# 03_RK808.net
KiCad netlist of a schematic drawn in Altium Designer
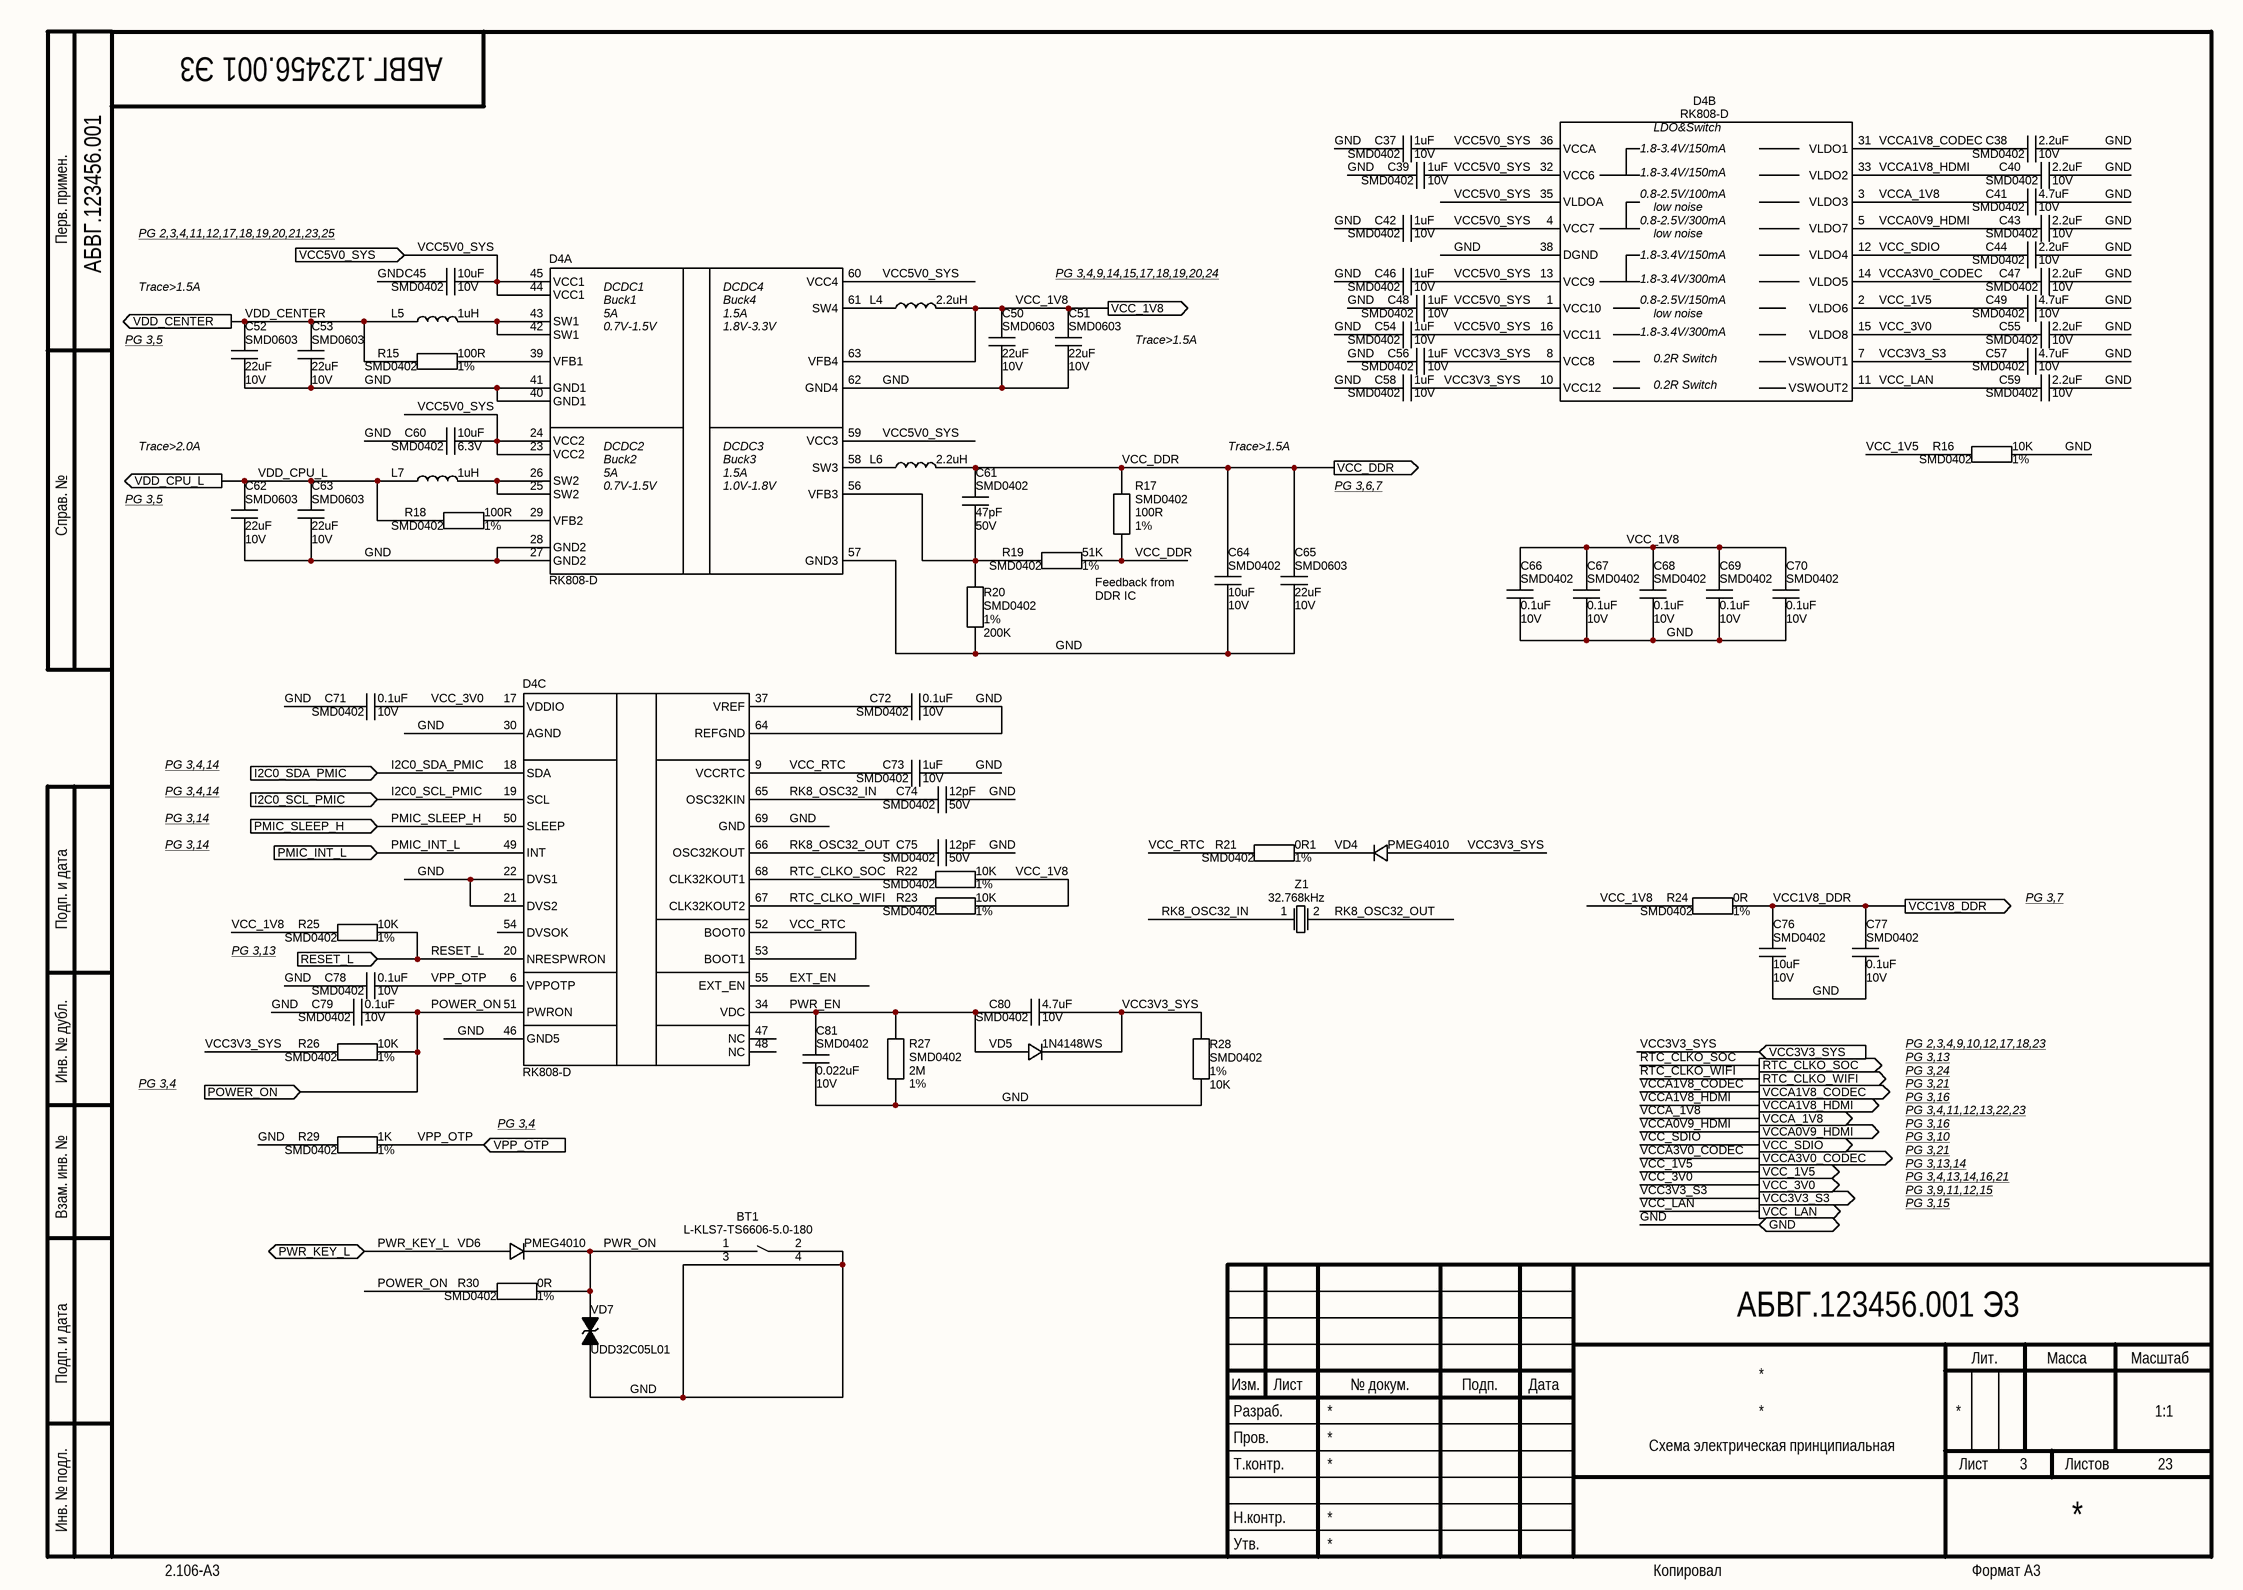
[diagram p0: 03 RK808.SchDoc]

(export (version "E")
  (design (tool "Eeschema 10.0.6"))
  (components
    (comp (ref "BT1")
      (value "L-KLS7-TS6606-5.0-180")
      (footprint "Didur_PcbLib_1:L-KLS7-TS6606-5.0-180")
      (libsource (lib "Didur_SchLib_1") (part "Button_Corner_4pin"))
    )
    (comp (ref "C37")
      (value "1uF")
      (footprint "Didur_PcbLib_1:CAP_SMD_0402")
      (fields
        (field (name "PACKAGE") "SMD0402")
        (field (name "PARTNUMBER") "CC0402KRX5R6BB105")
        (field (name "VOLTAGE") "10V")
      )
      (libsource (lib "Didur_SchLib_1") (part "Ceramic_Cap"))
    )
    (comp (ref "C38")
      (value "2.2uF")
      (footprint "Didur_PcbLib_1:CAP_SMD_0402")
      (fields
        (field (name "PACKAGE") "SMD0402")
        (field (name "PARTNUMBER") "CC0402KRX5R6BB225")
        (field (name "VOLTAGE") "10V")
      )
      (libsource (lib "Didur_SchLib_1") (part "Ceramic_Cap"))
    )
    (comp (ref "C39")
      (value "1uF")
      (footprint "Didur_PcbLib_1:CAP_SMD_0402")
      (fields
        (field (name "PACKAGE") "SMD0402")
        (field (name "PARTNUMBER") "CC0402KRX5R6BB105")
        (field (name "VOLTAGE") "10V")
      )
      (libsource (lib "Didur_SchLib_1") (part "Ceramic_Cap"))
    )
    (comp (ref "C40")
      (value "2.2uF")
      (footprint "Didur_PcbLib_1:CAP_SMD_0402")
      (fields
        (field (name "PACKAGE") "SMD0402")
        (field (name "PARTNUMBER") "CC0402KRX5R6BB225")
        (field (name "VOLTAGE") "10V")
      )
      (libsource (lib "Didur_SchLib_1") (part "Ceramic_Cap"))
    )
    (comp (ref "C41")
      (value "4.7uF")
      (footprint "Didur_PcbLib_1:CAP_SMD_0402")
      (fields
        (field (name "PACKAGE") "SMD0402")
        (field (name "PARTNUMBER") "CL05A475KP5NRNC")
        (field (name "VOLTAGE") "10V")
      )
      (libsource (lib "Didur_SchLib_1") (part "Ceramic_Cap"))
    )
    (comp (ref "C42")
      (value "1uF")
      (footprint "Didur_PcbLib_1:CAP_SMD_0402")
      (fields
        (field (name "PACKAGE") "SMD0402")
        (field (name "PARTNUMBER") "CC0402KRX5R6BB105")
        (field (name "VOLTAGE") "10V")
      )
      (libsource (lib "Didur_SchLib_1") (part "Ceramic_Cap"))
    )
    (comp (ref "C43")
      (value "2.2uF")
      (footprint "Didur_PcbLib_1:CAP_SMD_0402")
      (fields
        (field (name "PACKAGE") "SMD0402")
        (field (name "PARTNUMBER") "CC0402KRX5R6BB225")
        (field (name "VOLTAGE") "10V")
      )
      (libsource (lib "Didur_SchLib_1") (part "Ceramic_Cap"))
    )
    (comp (ref "C44")
      (value "2.2uF")
      (footprint "Didur_PcbLib_1:CAP_SMD_0402")
      (fields
        (field (name "PACKAGE") "SMD0402")
        (field (name "PARTNUMBER") "CC0402KRX5R6BB225")
        (field (name "VOLTAGE") "10V")
      )
      (libsource (lib "Didur_SchLib_1") (part "Ceramic_Cap"))
    )
    (comp (ref "C45")
      (value "10uF")
      (footprint "Didur_PcbLib_1:CAP_SMD_0402")
      (fields
        (field (name "PACKAGE") "SMD0402")
        (field (name "PARTNUMBER") "CC0402MRX5R6BB106")
        (field (name "VOLTAGE") "10V")
      )
      (libsource (lib "Didur_SchLib_1") (part "Ceramic_Cap"))
    )
    (comp (ref "C46")
      (value "1uF")
      (footprint "Didur_PcbLib_1:CAP_SMD_0402")
      (fields
        (field (name "PACKAGE") "SMD0402")
        (field (name "PARTNUMBER") "CC0402KRX5R6BB105")
        (field (name "VOLTAGE") "10V")
      )
      (libsource (lib "Didur_SchLib_1") (part "Ceramic_Cap"))
    )
    (comp (ref "C47")
      (value "2.2uF")
      (footprint "Didur_PcbLib_1:CAP_SMD_0402")
      (fields
        (field (name "PACKAGE") "SMD0402")
        (field (name "PARTNUMBER") "CC0402KRX5R6BB225")
        (field (name "VOLTAGE") "10V")
      )
      (libsource (lib "Didur_SchLib_1") (part "Ceramic_Cap"))
    )
    (comp (ref "C48")
      (value "1uF")
      (footprint "Didur_PcbLib_1:CAP_SMD_0402")
      (fields
        (field (name "PACKAGE") "SMD0402")
        (field (name "PARTNUMBER") "CC0402KRX5R6BB105")
        (field (name "VOLTAGE") "10V")
      )
      (libsource (lib "Didur_SchLib_1") (part "Ceramic_Cap"))
    )
    (comp (ref "C49")
      (value "4.7uF")
      (footprint "Didur_PcbLib_1:CAP_SMD_0402")
      (fields
        (field (name "PACKAGE") "SMD0402")
        (field (name "PARTNUMBER") "CL05A475KP5NRNC")
        (field (name "VOLTAGE") "10V")
      )
      (libsource (lib "Didur_SchLib_1") (part "Ceramic_Cap"))
    )
    (comp (ref "C50")
      (value "22uF")
      (footprint "CAP_SMD_0603")
      (fields
        (field (name "PACKAGE") "SMD0603")
        (field (name "PARTNUMBER") "CL10A226MP8NUNE")
        (field (name "VOLTAGE") "10V")
      )
      (libsource (lib "Didur_SchLib_1") (part "Ceramic_Cap"))
    )
    (comp (ref "C51")
      (value "22uF")
      (footprint "CAP_SMD_0603")
      (fields
        (field (name "PACKAGE") "SMD0603")
        (field (name "PARTNUMBER") "CL10A226MP8NUNE")
        (field (name "VOLTAGE") "10V")
      )
      (libsource (lib "Didur_SchLib_1") (part "Ceramic_Cap"))
    )
    (comp (ref "C52")
      (value "22uF")
      (footprint "CAP_SMD_0603")
      (fields
        (field (name "PACKAGE") "SMD0603")
        (field (name "PARTNUMBER") "CL10A226MP8NUNE")
        (field (name "VOLTAGE") "10V")
      )
      (libsource (lib "Didur_SchLib_1") (part "Ceramic_Cap"))
    )
    (comp (ref "C53")
      (value "22uF")
      (footprint "CAP_SMD_0603")
      (fields
        (field (name "PACKAGE") "SMD0603")
        (field (name "PARTNUMBER") "CL10A226MP8NUNE")
        (field (name "VOLTAGE") "10V")
      )
      (libsource (lib "Didur_SchLib_1") (part "Ceramic_Cap"))
    )
    (comp (ref "C54")
      (value "1uF")
      (footprint "Didur_PcbLib_1:CAP_SMD_0402")
      (fields
        (field (name "PACKAGE") "SMD0402")
        (field (name "PARTNUMBER") "CC0402KRX5R6BB105")
        (field (name "VOLTAGE") "10V")
      )
      (libsource (lib "Didur_SchLib_1") (part "Ceramic_Cap"))
    )
    (comp (ref "C55")
      (value "2.2uF")
      (footprint "Didur_PcbLib_1:CAP_SMD_0402")
      (fields
        (field (name "PACKAGE") "SMD0402")
        (field (name "PARTNUMBER") "CC0402KRX5R6BB225")
        (field (name "VOLTAGE") "10V")
      )
      (libsource (lib "Didur_SchLib_1") (part "Ceramic_Cap"))
    )
    (comp (ref "C56")
      (value "1uF")
      (footprint "Didur_PcbLib_1:CAP_SMD_0402")
      (fields
        (field (name "PACKAGE") "SMD0402")
        (field (name "PARTNUMBER") "CC0402KRX5R6BB105")
        (field (name "VOLTAGE") "10V")
      )
      (libsource (lib "Didur_SchLib_1") (part "Ceramic_Cap"))
    )
    (comp (ref "C57")
      (value "4.7uF")
      (footprint "Didur_PcbLib_1:CAP_SMD_0402")
      (fields
        (field (name "PACKAGE") "SMD0402")
        (field (name "PARTNUMBER") "CL05A475KP5NRNC")
        (field (name "VOLTAGE") "10V")
      )
      (libsource (lib "Didur_SchLib_1") (part "Ceramic_Cap"))
    )
    (comp (ref "C58")
      (value "1uF")
      (footprint "Didur_PcbLib_1:CAP_SMD_0402")
      (fields
        (field (name "PACKAGE") "SMD0402")
        (field (name "PARTNUMBER") "CC0402KRX5R6BB105")
        (field (name "VOLTAGE") "10V")
      )
      (libsource (lib "Didur_SchLib_1") (part "Ceramic_Cap"))
    )
    (comp (ref "C59")
      (value "2.2uF")
      (footprint "Didur_PcbLib_1:CAP_SMD_0402")
      (fields
        (field (name "PACKAGE") "SMD0402")
        (field (name "PARTNUMBER") "CC0402KRX5R6BB225")
        (field (name "VOLTAGE") "10V")
      )
      (libsource (lib "Didur_SchLib_1") (part "Ceramic_Cap"))
    )
    (comp (ref "C60")
      (value "10uF")
      (footprint "Didur_PcbLib_1:CAP_SMD_0402")
      (fields
        (field (name "PACKAGE") "SMD0402")
        (field (name "PARTNUMBER") "CC0402MRX5R6BB106")
        (field (name "VOLTAGE") "6.3V")
      )
      (libsource (lib "Didur_SchLib_1") (part "Ceramic_Cap"))
    )
    (comp (ref "C61")
      (value "47pF")
      (footprint "Didur_PcbLib_1:CAP_SMD_0402")
      (fields
        (field (name "PACKAGE") "SMD0402")
        (field (name "PARTNUMBER") "CC0402FRNPO9BN470")
        (field (name "VOLTAGE") "50V")
      )
      (libsource (lib "Didur_SchLib_1") (part "Ceramic_Cap"))
    )
    (comp (ref "C62")
      (value "22uF")
      (footprint "CAP_SMD_0603")
      (fields
        (field (name "PACKAGE") "SMD0603")
        (field (name "PARTNUMBER") "CL10A226MP8NUNE")
        (field (name "VOLTAGE") "10V")
      )
      (libsource (lib "Didur_SchLib_1") (part "Ceramic_Cap"))
    )
    (comp (ref "C63")
      (value "22uF")
      (footprint "CAP_SMD_0603")
      (fields
        (field (name "PACKAGE") "SMD0603")
        (field (name "PARTNUMBER") "CL10A226MP8NUNE")
        (field (name "VOLTAGE") "10V")
      )
      (libsource (lib "Didur_SchLib_1") (part "Ceramic_Cap"))
    )
    (comp (ref "C64")
      (value "10uF")
      (footprint "Didur_PcbLib_1:CAP_SMD_0402")
      (fields
        (field (name "PACKAGE") "SMD0402")
        (field (name "PARTNUMBER") "CC0402MRX5R6BB106")
        (field (name "VOLTAGE") "10V")
      )
      (libsource (lib "Didur_SchLib_1") (part "Ceramic_Cap"))
    )
    (comp (ref "C65")
      (value "22uF")
      (footprint "CAP_SMD_0603")
      (fields
        (field (name "PACKAGE") "SMD0603")
        (field (name "PARTNUMBER") "CL10A226MP8NUNE")
        (field (name "VOLTAGE") "10V")
      )
      (libsource (lib "Didur_SchLib_1") (part "Ceramic_Cap"))
    )
    (comp (ref "C66")
      (value "0.1uF")
      (footprint "Didur_PcbLib_1:CAP_SMD_0402")
      (fields
        (field (name "PACKAGE") "SMD0402")
        (field (name "PARTNUMBER") "CC0402KRX5R6BB104")
        (field (name "VOLTAGE") "10V")
      )
      (libsource (lib "Didur_SchLib_1") (part "Ceramic_Cap"))
    )
    (comp (ref "C67")
      (value "0.1uF")
      (footprint "Didur_PcbLib_1:CAP_SMD_0402")
      (fields
        (field (name "PACKAGE") "SMD0402")
        (field (name "PARTNUMBER") "CC0402KRX5R6BB104")
        (field (name "VOLTAGE") "10V")
      )
      (libsource (lib "Didur_SchLib_1") (part "Ceramic_Cap"))
    )
    (comp (ref "C68")
      (value "0.1uF")
      (footprint "Didur_PcbLib_1:CAP_SMD_0402")
      (fields
        (field (name "PACKAGE") "SMD0402")
        (field (name "PARTNUMBER") "CC0402KRX5R6BB104")
        (field (name "VOLTAGE") "10V")
      )
      (libsource (lib "Didur_SchLib_1") (part "Ceramic_Cap"))
    )
    (comp (ref "C69")
      (value "0.1uF")
      (footprint "Didur_PcbLib_1:CAP_SMD_0402")
      (fields
        (field (name "PACKAGE") "SMD0402")
        (field (name "PARTNUMBER") "CC0402KRX5R6BB104")
        (field (name "VOLTAGE") "10V")
      )
      (libsource (lib "Didur_SchLib_1") (part "Ceramic_Cap"))
    )
    (comp (ref "C70")
      (value "0.1uF")
      (footprint "Didur_PcbLib_1:CAP_SMD_0402")
      (fields
        (field (name "PACKAGE") "SMD0402")
        (field (name "PARTNUMBER") "CC0402KRX5R6BB104")
        (field (name "VOLTAGE") "10V")
      )
      (libsource (lib "Didur_SchLib_1") (part "Ceramic_Cap"))
    )
    (comp (ref "C71")
      (value "0.1uF")
      (footprint "Didur_PcbLib_1:CAP_SMD_0402")
      (fields
        (field (name "PACKAGE") "SMD0402")
        (field (name "PARTNUMBER") "CC0402KRX5R6BB104")
        (field (name "VOLTAGE") "10V")
      )
      (libsource (lib "Didur_SchLib_1") (part "Ceramic_Cap"))
    )
    (comp (ref "C72")
      (value "0.1uF")
      (footprint "Didur_PcbLib_1:CAP_SMD_0402")
      (fields
        (field (name "PACKAGE") "SMD0402")
        (field (name "PARTNUMBER") "CC0402KRX5R6BB104")
        (field (name "VOLTAGE") "10V")
      )
      (libsource (lib "Didur_SchLib_1") (part "Ceramic_Cap"))
    )
    (comp (ref "C73")
      (value "1uF")
      (footprint "Didur_PcbLib_1:CAP_SMD_0402")
      (fields
        (field (name "PACKAGE") "SMD0402")
        (field (name "PARTNUMBER") "CC0402KRX5R6BB105")
        (field (name "VOLTAGE") "10V")
      )
      (libsource (lib "Didur_SchLib_1") (part "Ceramic_Cap"))
    )
    (comp (ref "C74")
      (value "12pF")
      (footprint "Didur_PcbLib_1:CAP_SMD_0402")
      (fields
        (field (name "PACKAGE") "SMD0402")
        (field (name "PARTNUMBER") "CC0402JRNPO9BN120")
        (field (name "VOLTAGE") "50V")
      )
      (libsource (lib "Didur_SchLib_1") (part "Ceramic_Cap"))
    )
    (comp (ref "C75")
      (value "12pF")
      (footprint "Didur_PcbLib_1:CAP_SMD_0402")
      (fields
        (field (name "PACKAGE") "SMD0402")
        (field (name "PARTNUMBER") "CC0402JRNPO9BN120")
        (field (name "VOLTAGE") "50V")
      )
      (libsource (lib "Didur_SchLib_1") (part "Ceramic_Cap"))
    )
    (comp (ref "C76")
      (value "10uF")
      (footprint "Didur_PcbLib_1:CAP_SMD_0402")
      (fields
        (field (name "PACKAGE") "SMD0402")
        (field (name "PARTNUMBER") "CC0402MRX5R6BB106")
        (field (name "VOLTAGE") "10V")
      )
      (libsource (lib "Didur_SchLib_1") (part "Ceramic_Cap"))
    )
    (comp (ref "C77")
      (value "0.1uF")
      (footprint "Didur_PcbLib_1:CAP_SMD_0402")
      (fields
        (field (name "PACKAGE") "SMD0402")
        (field (name "PARTNUMBER") "CC0402KRX5R6BB104")
        (field (name "VOLTAGE") "10V")
      )
      (libsource (lib "Didur_SchLib_1") (part "Ceramic_Cap"))
    )
    (comp (ref "C78")
      (value "0.1uF")
      (footprint "Didur_PcbLib_1:CAP_SMD_0402")
      (fields
        (field (name "PACKAGE") "SMD0402")
        (field (name "PARTNUMBER") "CC0402KRX5R6BB104")
        (field (name "VOLTAGE") "10V")
      )
      (libsource (lib "Didur_SchLib_1") (part "Ceramic_Cap"))
    )
    (comp (ref "C79")
      (value "0.1uF")
      (footprint "Didur_PcbLib_1:CAP_SMD_0402")
      (fields
        (field (name "PACKAGE") "SMD0402")
        (field (name "PARTNUMBER") "CC0402KRX5R6BB104")
        (field (name "VOLTAGE") "10V")
      )
      (libsource (lib "Didur_SchLib_1") (part "Ceramic_Cap"))
    )
    (comp (ref "C80")
      (value "4.7uF")
      (footprint "Didur_PcbLib_1:CAP_SMD_0402")
      (fields
        (field (name "PACKAGE") "SMD0402")
        (field (name "PARTNUMBER") "CL05A475KP5NRNC")
        (field (name "VOLTAGE") "10V")
      )
      (libsource (lib "Didur_SchLib_1") (part "Ceramic_Cap"))
    )
    (comp (ref "C81")
      (value "0.022uF")
      (footprint "Didur_PcbLib_1:CAP_SMD_0402")
      (fields
        (field (name "PACKAGE") "SMD0402")
        (field (name "PARTNUMBER") "GRM155R61A223KA01D")
        (field (name "VOLTAGE") "10V")
      )
      (libsource (lib "Didur_SchLib_1") (part "Ceramic_Cap"))
    )
    (comp (ref "D4")
      (value "RK808-D")
      (footprint "Didur_PcbLib_1:QFN35P700X700X80-69N")
      (libsource (lib "Didur_SchLib_1") (part "RK808-D"))
    )
    (comp (ref "L4")
      (value "2.2uH")
      (footprint "Didur_PcbLib_1:HEI252012A")
      (fields (field (name "PARTNUMBER") "HEI252012A-2R2M-Q8") (field (name "Comment") "Value"))
      (libsource (lib "Didur_SchLib_1") (part "Inductor_smal"))
    )
    (comp (ref "L5")
      (value "1uH")
      (footprint "Didur_PcbLib_1:HEI252012A")
      (fields (field (name "PARTNUMBER") "HEI252012A-1R0M-Q8") (field (name "Comment") "Value"))
      (libsource (lib "Didur_SchLib_1") (part "Inductor_smal"))
    )
    (comp (ref "L6")
      (value "2.2uH")
      (footprint "Didur_PcbLib_1:HEI252012A")
      (fields (field (name "PARTNUMBER") "HEI252012A-2R2M-Q8") (field (name "Comment") "Value"))
      (libsource (lib "Didur_SchLib_1") (part "Inductor_smal"))
    )
    (comp (ref "L7")
      (value "1uH")
      (footprint "Didur_PcbLib_1:HEI252012A")
      (fields (field (name "PARTNUMBER") "HEI252012A-1R0M-Q8") (field (name "Comment") "Value"))
      (libsource (lib "Didur_SchLib_1") (part "Inductor_smal"))
    )
    (comp (ref "R15")
      (value "100R")
      (footprint "Didur_PcbLib_1:RES_SMD_0402")
      (fields
        (field (name "PACKAGE") "SMD0402")
        (field (name "PARTNUMBER") "RC0402FR-07100RL")
        (field (name "TOLERANCE") "1%")
      )
      (libsource (lib "Didur_SchLib_1") (part "Chip_Res"))
    )
    (comp (ref "R16")
      (value "10K")
      (footprint "Didur_PcbLib_1:RES_SMD_0402")
      (fields
        (field (name "PACKAGE") "SMD0402")
        (field (name "PARTNUMBER") "RC0402FR-0710KL")
        (field (name "TOLERANCE") "1%")
      )
      (libsource (lib "") (part "Chip_Res_2"))
    )
    (comp (ref "R17")
      (value "100R")
      (footprint "Didur_PcbLib_1:RES_SMD_0402")
      (fields
        (field (name "PACKAGE") "SMD0402")
        (field (name "PARTNUMBER") "RC0402FR-07100RL")
        (field (name "TOLERANCE") "1%")
      )
      (libsource (lib "") (part "Chip_Res_1"))
    )
    (comp (ref "R18")
      (value "100R")
      (footprint "Didur_PcbLib_1:RES_SMD_0402")
      (fields
        (field (name "PACKAGE") "SMD0402")
        (field (name "PARTNUMBER") "RC0402FR-07100RL")
        (field (name "TOLERANCE") "1%")
      )
      (libsource (lib "Didur_SchLib_1") (part "Chip_Res"))
    )
    (comp (ref "R19")
      (value "51K")
      (footprint "Didur_PcbLib_1:RES_SMD_0402")
      (fields
        (field (name "PACKAGE") "SMD0402")
        (field (name "PARTNUMBER") "RC0402FR-0751KL")
        (field (name "TOLERANCE") "1%")
      )
      (libsource (lib "") (part "Chip_Res_3"))
    )
    (comp (ref "R20")
      (value "200K")
      (footprint "Didur_PcbLib_1:RES_SMD_0402")
      (fields
        (field (name "PACKAGE") "SMD0402")
        (field (name "PARTNUMBER") "RC0402FR-07200KL")
        (field (name "TOLERANCE") "1%")
      )
      (libsource (lib "") (part "Chip_Res_1"))
    )
    (comp (ref "R21")
      (value "0R1")
      (footprint "Didur_PcbLib_1:RES_SMD_0402")
      (fields
        (field (name "PACKAGE") "SMD0402")
        (field (name "PARTNUMBER") "RL0402FR-070R1L")
        (field (name "TOLERANCE") "1%")
      )
      (libsource (lib "") (part "Chip_Res_1"))
    )
    (comp (ref "R22")
      (value "10K")
      (footprint "Didur_PcbLib_1:RES_SMD_0402")
      (fields
        (field (name "PACKAGE") "SMD0402")
        (field (name "PARTNUMBER") "RC0402FR-0710KL")
        (field (name "TOLERANCE") "1%")
      )
      (libsource (lib "") (part "Chip_Res_2"))
    )
    (comp (ref "R23")
      (value "10K")
      (footprint "Didur_PcbLib_1:RES_SMD_0402")
      (fields
        (field (name "PACKAGE") "SMD0402")
        (field (name "PARTNUMBER") "RC0402FR-0710KL")
        (field (name "TOLERANCE") "1%")
      )
      (libsource (lib "") (part "Chip_Res_2"))
    )
    (comp (ref "R24")
      (value "0R")
      (footprint "Didur_PcbLib_1:RES_SMD_0402")
      (fields
        (field (name "PACKAGE") "SMD0402")
        (field (name "PARTNUMBER") "RC0402FR-070RL")
        (field (name "TOLERANCE") "1%")
      )
      (libsource (lib "") (part "Chip_Res_1"))
    )
    (comp (ref "R25")
      (value "10K")
      (footprint "Didur_PcbLib_1:RES_SMD_0402")
      (fields
        (field (name "PACKAGE") "SMD0402")
        (field (name "PARTNUMBER") "RC0402FR-0710KL")
        (field (name "TOLERANCE") "1%")
      )
      (libsource (lib "") (part "Chip_Res_2"))
    )
    (comp (ref "R26")
      (value "10K")
      (footprint "Didur_PcbLib_1:RES_SMD_0402")
      (fields
        (field (name "PACKAGE") "SMD0402")
        (field (name "PARTNUMBER") "RC0402FR-0710KL")
        (field (name "TOLERANCE") "1%")
      )
      (libsource (lib "") (part "Chip_Res_2"))
    )
    (comp (ref "R27")
      (value "2M")
      (footprint "Didur_PcbLib_1:RES_SMD_0402")
      (fields
        (field (name "PACKAGE") "SMD0402")
        (field (name "PARTNUMBER") "RC0402FR-072ML")
        (field (name "TOLERANCE") "1%")
      )
      (libsource (lib "") (part "Chip_Res_1"))
    )
    (comp (ref "R28")
      (value "10K")
      (footprint "Didur_PcbLib_1:RES_SMD_0402")
      (fields
        (field (name "PACKAGE") "SMD0402")
        (field (name "PARTNUMBER") "RC0402FR-0710KL")
        (field (name "TOLERANCE") "1%")
      )
      (libsource (lib "Didur_SchLib_1") (part "Chip_Res"))
    )
    (comp (ref "R29")
      (value "1K")
      (footprint "Didur_PcbLib_1:RES_SMD_0402")
      (fields
        (field (name "PACKAGE") "SMD0402")
        (field (name "PARTNUMBER") "RC0402FR-071KL")
        (field (name "TOLERANCE") "1%")
      )
      (libsource (lib "Didur_SchLib_1") (part "Chip_Res"))
    )
    (comp (ref "R30")
      (value "0R")
      (footprint "Didur_PcbLib_1:RES_SMD_0402")
      (fields
        (field (name "PACKAGE") "SMD0402")
        (field (name "PARTNUMBER") "RC0402FR-070RL")
        (field (name "TOLERANCE") "1%")
      )
      (libsource (lib "") (part "Chip_Res_1"))
    )
    (comp (ref "VD4")
      (value "PMEG4010")
      (footprint "SOD323")
      (fields (field (name "PARTNUMBER") "PMEG4010CEJ.115") (field (name "Comment") "Diode"))
      (libsource (lib "Didur_SchLib_1") (part "Diode"))
    )
    (comp (ref "VD5")
      (value "1N4148WS")
      (footprint "SOD323")
      (fields (field (name "Comment") "Diode"))
      (libsource (lib "Didur_SchLib_1") (part "Diode"))
    )
    (comp (ref "VD6")
      (value "PMEG4010")
      (footprint "SOD323")
      (fields (field (name "PARTNUMBER") "PMEG4010CEJ.115") (field (name "Comment") "Diode"))
      (libsource (lib "Didur_SchLib_1") (part "Diode"))
    )
    (comp (ref "VD7")
      (value "UDD32C05L01")
      (footprint "Didur_PcbLib_1:SOD323")
      (fields (field (name "Comment") "TVS_Diode"))
      (libsource (lib "Didur_SchLib_1") (part "TVS_Diode"))
    )
    (comp (ref "Z1")
      (value "32.768kHz")
      (footprint "Didur_PcbLib_1:TSX3215")
      (fields (field (name "PARTNUMBER") "SJK-7L-32.768-12.5-20-70-C") (field (name "Comment") "Value"))
      (libsource (lib "Didur_SchLib_1") (part "OSC3215"))
    )
  )
  (nets
    (net (code "1") (name "/EXT_EN") (class "Default")
      (node (ref "D4") (pin "55") (pinfunction "EXT_EN_55") (pintype "passive"))
    )
    (net (code "2") (name "/GND") (class "Default")
      (node (ref "BT1") (pin "2") (pinfunction "2_2") (pintype "passive"))
      (node (ref "BT1") (pin "3") (pinfunction "3_3") (pintype "passive"))
      (node (ref "BT1") (pin "4") (pinfunction "4_4") (pintype "passive"))
      (node (ref "C37") (pin "2") (pinfunction "2_2") (pintype "power_in"))
      (node (ref "C38") (pin "2") (pinfunction "2_2") (pintype "power_in"))
      (node (ref "C39") (pin "2") (pinfunction "2_2") (pintype "power_in"))
      (node (ref "C40") (pin "2") (pinfunction "2_2") (pintype "power_in"))
      (node (ref "C41") (pin "2") (pinfunction "2_2") (pintype "power_in"))
      (node (ref "C42") (pin "2") (pinfunction "2_2") (pintype "power_in"))
      (node (ref "C43") (pin "2") (pinfunction "2_2") (pintype "power_in"))
      (node (ref "C44") (pin "2") (pinfunction "2_2") (pintype "power_in"))
      (node (ref "C45") (pin "1") (pinfunction "1_1") (pintype "power_in"))
      (node (ref "C46") (pin "2") (pinfunction "2_2") (pintype "power_in"))
      (node (ref "C47") (pin "2") (pinfunction "2_2") (pintype "power_in"))
      (node (ref "C48") (pin "2") (pinfunction "2_2") (pintype "power_in"))
      (node (ref "C49") (pin "2") (pinfunction "2_2") (pintype "power_in"))
      (node (ref "C50") (pin "1") (pinfunction "1_1") (pintype "power_in"))
      (node (ref "C51") (pin "1") (pinfunction "1_1") (pintype "power_in"))
      (node (ref "C52") (pin "1") (pinfunction "1_1") (pintype "power_in"))
      (node (ref "C53") (pin "1") (pinfunction "1_1") (pintype "power_in"))
      (node (ref "C54") (pin "2") (pinfunction "2_2") (pintype "power_in"))
      (node (ref "C55") (pin "2") (pinfunction "2_2") (pintype "power_in"))
      (node (ref "C56") (pin "2") (pinfunction "2_2") (pintype "power_in"))
      (node (ref "C57") (pin "2") (pinfunction "2_2") (pintype "power_in"))
      (node (ref "C58") (pin "2") (pinfunction "2_2") (pintype "power_in"))
      (node (ref "C59") (pin "2") (pinfunction "2_2") (pintype "power_in"))
      (node (ref "C60") (pin "2") (pinfunction "2_2") (pintype "power_in"))
      (node (ref "C62") (pin "1") (pinfunction "1_1") (pintype "power_in"))
      (node (ref "C63") (pin "1") (pinfunction "1_1") (pintype "power_in"))
      (node (ref "C64") (pin "2") (pinfunction "2_2") (pintype "power_in"))
      (node (ref "C65") (pin "1") (pinfunction "1_1") (pintype "power_in"))
      (node (ref "C66") (pin "2") (pinfunction "2_2") (pintype "power_in"))
      (node (ref "C67") (pin "2") (pinfunction "2_2") (pintype "power_in"))
      (node (ref "C68") (pin "2") (pinfunction "2_2") (pintype "power_in"))
      (node (ref "C69") (pin "2") (pinfunction "2_2") (pintype "power_in"))
      (node (ref "C70") (pin "2") (pinfunction "2_2") (pintype "power_in"))
      (node (ref "C71") (pin "1") (pinfunction "1_1") (pintype "power_in"))
      (node (ref "C72") (pin "2") (pinfunction "2_2") (pintype "power_in"))
      (node (ref "C73") (pin "1") (pinfunction "1_1") (pintype "power_in"))
      (node (ref "C74") (pin "1") (pinfunction "1_1") (pintype "power_in"))
      (node (ref "C75") (pin "1") (pinfunction "1_1") (pintype "power_in"))
      (node (ref "C76") (pin "2") (pinfunction "2_2") (pintype "power_in"))
      (node (ref "C77") (pin "2") (pinfunction "2_2") (pintype "power_in"))
      (node (ref "C78") (pin "1") (pinfunction "1_1") (pintype "power_in"))
      (node (ref "C79") (pin "1") (pinfunction "1_1") (pintype "power_in"))
      (node (ref "C81") (pin "2") (pinfunction "2_2") (pintype "power_in"))
      (node (ref "D4") (pin "21") (pinfunction "DVS2_21") (pintype "passive"))
      (node (ref "D4") (pin "22") (pinfunction "DVS1_22") (pintype "passive"))
      (node (ref "D4") (pin "27") (pinfunction "GND2_27") (pintype "passive"))
      (node (ref "D4") (pin "28") (pinfunction "GND2_28") (pintype "passive"))
      (node (ref "D4") (pin "30") (pinfunction "AGND_30") (pintype "passive"))
      (node (ref "D4") (pin "38") (pinfunction "DGND_38") (pintype "passive"))
      (node (ref "D4") (pin "40") (pinfunction "GND1_40") (pintype "passive"))
      (node (ref "D4") (pin "41") (pinfunction "GND1_41") (pintype "passive"))
      (node (ref "D4") (pin "46") (pinfunction "GND5_46") (pintype "passive"))
      (node (ref "D4") (pin "57") (pinfunction "GND3_57") (pintype "passive"))
      (node (ref "D4") (pin "62") (pinfunction "GND4_62") (pintype "passive"))
      (node (ref "D4") (pin "64") (pinfunction "REFGND_64") (pintype "passive"))
      (node (ref "D4") (pin "69") (pinfunction "GND_69") (pintype "passive"))
      (node (ref "R16") (pin "1") (pinfunction "1_1") (pintype "passive"))
      (node (ref "R20") (pin "1") (pinfunction "1_1") (pintype "passive"))
      (node (ref "R27") (pin "1") (pinfunction "1_1") (pintype "passive"))
      (node (ref "R28") (pin "1") (pinfunction "1_1") (pintype "passive"))
      (node (ref "R29") (pin "1") (pinfunction "1_1") (pintype "passive"))
      (node (ref "VD7") (pin "1") (pinfunction "A_1") (pintype "passive"))
    )
    (net (code "3") (name "/I2C0_SCL_PMIC") (class "Default")
      (node (ref "D4") (pin "19") (pinfunction "SCL_19") (pintype "passive"))
    )
    (net (code "4") (name "/I2C0_SDA_PMIC") (class "Default")
      (node (ref "D4") (pin "18") (pinfunction "SDA_18") (pintype "passive"))
    )
    (net (code "5") (name "/PMIC_INT_L") (class "Default")
      (node (ref "D4") (pin "49") (pinfunction "INT_49") (pintype "passive"))
    )
    (net (code "6") (name "/PMIC_SLEEP_H") (class "Default")
      (node (ref "D4") (pin "50") (pinfunction "SLEEP_50") (pintype "passive"))
    )
    (net (code "7") (name "/POWER_ON") (class "Default")
      (node (ref "C79") (pin "2") (pinfunction "2_2") (pintype "power_in"))
      (node (ref "D4") (pin "51") (pinfunction "PWRON_51") (pintype "passive"))
      (node (ref "R26") (pin "1") (pinfunction "1_1") (pintype "passive"))
      (node (ref "R30") (pin "1") (pinfunction "1_1") (pintype "passive"))
    )
    (net (code "8") (name "/PWR_EN") (class "Default")
      (node (ref "C80") (pin "1") (pinfunction "1_1") (pintype "power_in"))
      (node (ref "C81") (pin "1") (pinfunction "1_1") (pintype "power_in"))
      (node (ref "D4") (pin "34") (pinfunction "VDC_34") (pintype "passive"))
      (node (ref "R27") (pin "2") (pinfunction "2_2") (pintype "passive"))
      (node (ref "VD5") (pin "1") (pinfunction "A_1") (pintype "passive"))
    )
    (net (code "9") (name "/PWR_KEY_L") (class "Default")
      (node (ref "VD6") (pin "1") (pinfunction "A_1") (pintype "passive"))
    )
    (net (code "10") (name "/PWR_ON") (class "Default")
      (node (ref "BT1") (pin "1") (pinfunction "1_1") (pintype "passive"))
      (node (ref "R30") (pin "2") (pinfunction "2_2") (pintype "passive"))
      (node (ref "VD6") (pin "2") (pinfunction "C_2") (pintype "passive"))
      (node (ref "VD7") (pin "2") (pinfunction "C_2") (pintype "passive"))
    )
    (net (code "11") (name "/RESET_L") (class "Default")
      (node (ref "D4") (pin "20") (pinfunction "NRESPWRON_20") (pintype "passive"))
      (node (ref "R25") (pin "1") (pinfunction "1_1") (pintype "passive"))
    )
    (net (code "12") (name "/RK8_OSC32_IN") (class "Default")
      (node (ref "C74") (pin "2") (pinfunction "2_2") (pintype "power_in"))
      (node (ref "D4") (pin "65") (pinfunction "OSC32KIN_65") (pintype "passive"))
      (node (ref "Z1") (pin "1") (pinfunction "1_1") (pintype "passive"))
    )
    (net (code "13") (name "/RK8_OSC32_OUT") (class "Default")
      (node (ref "C75") (pin "2") (pinfunction "2_2") (pintype "power_in"))
      (node (ref "D4") (pin "66") (pinfunction "OSC32KOUT_66") (pintype "passive"))
      (node (ref "Z1") (pin "2") (pinfunction "2_2") (pintype "passive"))
    )
    (net (code "14") (name "/RTC_CLKO_SOC") (class "Default")
      (node (ref "D4") (pin "68") (pinfunction "CLK32KOUT1_68") (pintype "passive"))
      (node (ref "R22") (pin "2") (pinfunction "2_2") (pintype "passive"))
    )
    (net (code "15") (name "/RTC_CLKO_WIFI") (class "Default")
      (node (ref "D4") (pin "67") (pinfunction "CLK32KOUT2_67") (pintype "passive"))
      (node (ref "R23") (pin "2") (pinfunction "2_2") (pintype "passive"))
    )
    (net (code "16") (name "/VCC1V8_DDR") (class "Default")
      (node (ref "C76") (pin "1") (pinfunction "1_1") (pintype "power_in"))
      (node (ref "C77") (pin "1") (pinfunction "1_1") (pintype "power_in"))
      (node (ref "R24") (pin "2") (pinfunction "2_2") (pintype "passive"))
    )
    (net (code "17") (name "/VCC3V3_S3") (class "Default")
      (node (ref "C57") (pin "1") (pinfunction "1_1") (pintype "power_in"))
      (node (ref "D4") (pin "7") (pinfunction "VSWOUT1_7") (pintype "passive"))
    )
    (net (code "18") (name "/VCC3V3_SYS") (class "Default")
      (node (ref "C56") (pin "1") (pinfunction "1_1") (pintype "power_in"))
      (node (ref "C58") (pin "1") (pinfunction "1_1") (pintype "power_in"))
      (node (ref "C80") (pin "2") (pinfunction "2_2") (pintype "power_in"))
      (node (ref "D4") (pin "10") (pinfunction "VCC12_10") (pintype "passive"))
      (node (ref "D4") (pin "8") (pinfunction "VCC8_8") (pintype "passive"))
      (node (ref "R26") (pin "2") (pinfunction "2_2") (pintype "passive"))
      (node (ref "R28") (pin "2") (pinfunction "2_2") (pintype "passive"))
      (node (ref "VD4") (pin "1") (pinfunction "A_1") (pintype "passive"))
      (node (ref "VD5") (pin "2") (pinfunction "C_2") (pintype "passive"))
    )
    (net (code "19") (name "/VCC5V0_SYS") (class "Default")
      (node (ref "C37") (pin "1") (pinfunction "1_1") (pintype "power_in"))
      (node (ref "C39") (pin "1") (pinfunction "1_1") (pintype "power_in"))
      (node (ref "C42") (pin "1") (pinfunction "1_1") (pintype "power_in"))
      (node (ref "C45") (pin "2") (pinfunction "2_2") (pintype "power_in"))
      (node (ref "C46") (pin "1") (pinfunction "1_1") (pintype "power_in"))
      (node (ref "C48") (pin "1") (pinfunction "1_1") (pintype "power_in"))
      (node (ref "C54") (pin "1") (pinfunction "1_1") (pintype "power_in"))
      (node (ref "C60") (pin "1") (pinfunction "1_1") (pintype "power_in"))
      (node (ref "D4") (pin "1") (pinfunction "VCC10_1") (pintype "passive"))
      (node (ref "D4") (pin "13") (pinfunction "VCC9_13") (pintype "passive"))
      (node (ref "D4") (pin "16") (pinfunction "VCC11_16") (pintype "passive"))
      (node (ref "D4") (pin "23") (pinfunction "VCC2_23") (pintype "passive"))
      (node (ref "D4") (pin "24") (pinfunction "VCC2_24") (pintype "passive"))
      (node (ref "D4") (pin "32") (pinfunction "VCC6_32") (pintype "passive"))
      (node (ref "D4") (pin "35") (pinfunction "VLDOA_35") (pintype "passive"))
      (node (ref "D4") (pin "36") (pinfunction "VCCA_36") (pintype "passive"))
      (node (ref "D4") (pin "4") (pinfunction "VCC7_4") (pintype "passive"))
      (node (ref "D4") (pin "44") (pinfunction "VCC1_44") (pintype "passive"))
      (node (ref "D4") (pin "45") (pinfunction "VCC1_45") (pintype "passive"))
      (node (ref "D4") (pin "59") (pinfunction "VCC3_59") (pintype "passive"))
      (node (ref "D4") (pin "60") (pinfunction "VCC4_60") (pintype "passive"))
    )
    (net (code "20") (name "/VCCA0V9_HDMI") (class "Default")
      (node (ref "C43") (pin "1") (pinfunction "1_1") (pintype "power_in"))
      (node (ref "D4") (pin "5") (pinfunction "VLDO7_5") (pintype "passive"))
    )
    (net (code "21") (name "/VCCA1V8_CODEC") (class "Default")
      (node (ref "C38") (pin "1") (pinfunction "1_1") (pintype "power_in"))
      (node (ref "D4") (pin "31") (pinfunction "VLDO1_31") (pintype "passive"))
    )
    (net (code "22") (name "/VCCA1V8_HDMI") (class "Default")
      (node (ref "C40") (pin "1") (pinfunction "1_1") (pintype "power_in"))
      (node (ref "D4") (pin "33") (pinfunction "VLDO2_33") (pintype "passive"))
    )
    (net (code "23") (name "/VCCA3V0_CODEC") (class "Default")
      (node (ref "C47") (pin "1") (pinfunction "1_1") (pintype "power_in"))
      (node (ref "D4") (pin "14") (pinfunction "VLDO5_14") (pintype "passive"))
    )
    (net (code "24") (name "/VCCA_1V8") (class "Default")
      (node (ref "C41") (pin "1") (pinfunction "1_1") (pintype "power_in"))
      (node (ref "D4") (pin "3") (pinfunction "VLDO3_3") (pintype "passive"))
    )
    (net (code "25") (name "/VCC_1V5") (class "Default")
      (node (ref "C49") (pin "1") (pinfunction "1_1") (pintype "power_in"))
      (node (ref "D4") (pin "2") (pinfunction "VLDO6_2") (pintype "passive"))
      (node (ref "R16") (pin "2") (pinfunction "2_2") (pintype "passive"))
    )
    (net (code "26") (name "/VCC_1V8") (class "Default")
      (node (ref "C50") (pin "2") (pinfunction "2_2") (pintype "power_in"))
      (node (ref "C51") (pin "2") (pinfunction "2_2") (pintype "power_in"))
      (node (ref "C66") (pin "1") (pinfunction "1_1") (pintype "power_in"))
      (node (ref "C67") (pin "1") (pinfunction "1_1") (pintype "power_in"))
      (node (ref "C68") (pin "1") (pinfunction "1_1") (pintype "power_in"))
      (node (ref "C69") (pin "1") (pinfunction "1_1") (pintype "power_in"))
      (node (ref "C70") (pin "1") (pinfunction "1_1") (pintype "power_in"))
      (node (ref "D4") (pin "63") (pinfunction "VFB4_63") (pintype "passive"))
      (node (ref "L4") (pin "1") (pinfunction "1_1") (pintype "passive"))
      (node (ref "R22") (pin "1") (pinfunction "1_1") (pintype "passive"))
      (node (ref "R23") (pin "1") (pinfunction "1_1") (pintype "passive"))
      (node (ref "R24") (pin "1") (pinfunction "1_1") (pintype "passive"))
      (node (ref "R25") (pin "2") (pinfunction "2_2") (pintype "passive"))
    )
    (net (code "27") (name "/VCC_3V0") (class "Default")
      (node (ref "C55") (pin "1") (pinfunction "1_1") (pintype "power_in"))
      (node (ref "C71") (pin "2") (pinfunction "2_2") (pintype "power_in"))
      (node (ref "D4") (pin "15") (pinfunction "VLDO8_15") (pintype "passive"))
      (node (ref "D4") (pin "17") (pinfunction "VDDIO_17") (pintype "passive"))
    )
    (net (code "28") (name "/VCC_DDR") (class "Default")
      (node (ref "C61") (pin "1") (pinfunction "1_1") (pintype "power_in"))
      (node (ref "C64") (pin "1") (pinfunction "1_1") (pintype "power_in"))
      (node (ref "C65") (pin "2") (pinfunction "2_2") (pintype "power_in"))
      (node (ref "L6") (pin "1") (pinfunction "1_1") (pintype "passive"))
      (node (ref "R17") (pin "1") (pinfunction "1_1") (pintype "passive"))
      (node (ref "R17") (pin "2") (pinfunction "2_2") (pintype "passive"))
      (node (ref "R19") (pin "1") (pinfunction "1_1") (pintype "passive"))
    )
    (net (code "29") (name "/VCC_LAN") (class "Default")
      (node (ref "C59") (pin "1") (pinfunction "1_1") (pintype "power_in"))
      (node (ref "D4") (pin "11") (pinfunction "VSWOUT2_11") (pintype "passive"))
    )
    (net (code "30") (name "/VCC_RTC") (class "Default")
      (node (ref "C73") (pin "2") (pinfunction "2_2") (pintype "power_in"))
      (node (ref "D4") (pin "52") (pinfunction "BOOT0_52") (pintype "passive"))
      (node (ref "D4") (pin "53") (pinfunction "BOOT1_53") (pintype "passive"))
      (node (ref "D4") (pin "9") (pinfunction "VCCRTC_9") (pintype "passive"))
      (node (ref "R21") (pin "1") (pinfunction "1_1") (pintype "passive"))
    )
    (net (code "31") (name "/VCC_SDIO") (class "Default")
      (node (ref "C44") (pin "1") (pinfunction "1_1") (pintype "power_in"))
      (node (ref "D4") (pin "12") (pinfunction "VLDO4_12") (pintype "passive"))
    )
    (net (code "32") (name "/VDD_CENTER") (class "Default")
      (node (ref "C52") (pin "2") (pinfunction "2_2") (pintype "power_in"))
      (node (ref "C53") (pin "2") (pinfunction "2_2") (pintype "power_in"))
      (node (ref "L5") (pin "2") (pinfunction "2_2") (pintype "passive"))
      (node (ref "R15") (pin "1") (pinfunction "1_1") (pintype "passive"))
    )
    (net (code "33") (name "/VDD_CPU_L") (class "Default")
      (node (ref "C62") (pin "2") (pinfunction "2_2") (pintype "power_in"))
      (node (ref "C63") (pin "2") (pinfunction "2_2") (pintype "power_in"))
      (node (ref "L7") (pin "2") (pinfunction "2_2") (pintype "passive"))
      (node (ref "R18") (pin "1") (pinfunction "1_1") (pintype "passive"))
    )
    (net (code "34") (name "/VPP_OTP") (class "Default")
      (node (ref "C78") (pin "2") (pinfunction "2_2") (pintype "power_in"))
      (node (ref "D4") (pin "6") (pinfunction "VPPOTP_6") (pintype "passive"))
      (node (ref "R29") (pin "2") (pinfunction "2_2") (pintype "passive"))
    )
    (net (code "35") (name "Net-(D4A-SW1-Pad42)") (class "Default")
      (node (ref "D4") (pin "42") (pinfunction "SW1_42") (pintype "passive"))
      (node (ref "D4") (pin "43") (pinfunction "SW1_43") (pintype "passive"))
      (node (ref "L5") (pin "1") (pinfunction "1_1") (pintype "passive"))
    )
    (net (code "36") (name "Net-(D4A-SW2-Pad25)") (class "Default")
      (node (ref "D4") (pin "25") (pinfunction "SW2_25") (pintype "passive"))
      (node (ref "D4") (pin "26") (pinfunction "SW2_26") (pintype "passive"))
      (node (ref "L7") (pin "1") (pinfunction "1_1") (pintype "passive"))
    )
    (net (code "37") (name "Net-(D4A-SW3)") (class "Default")
      (node (ref "D4") (pin "58") (pinfunction "SW3_58") (pintype "passive"))
      (node (ref "L6") (pin "2") (pinfunction "2_2") (pintype "passive"))
    )
    (net (code "38") (name "Net-(D4A-SW4)") (class "Default")
      (node (ref "D4") (pin "61") (pinfunction "SW4_61") (pintype "passive"))
      (node (ref "L4") (pin "2") (pinfunction "2_2") (pintype "passive"))
    )
    (net (code "39") (name "Net-(D4A-VFB1)") (class "Default")
      (node (ref "D4") (pin "39") (pinfunction "VFB1_39") (pintype "passive"))
      (node (ref "R15") (pin "2") (pinfunction "2_2") (pintype "passive"))
    )
    (net (code "40") (name "Net-(D4A-VFB2)") (class "Default")
      (node (ref "D4") (pin "29") (pinfunction "VFB2_29") (pintype "passive"))
      (node (ref "R18") (pin "2") (pinfunction "2_2") (pintype "passive"))
    )
    (net (code "41") (name "Net-(D4A-VFB3)") (class "Default")
      (node (ref "C61") (pin "2") (pinfunction "2_2") (pintype "power_in"))
      (node (ref "D4") (pin "56") (pinfunction "VFB3_56") (pintype "passive"))
      (node (ref "R19") (pin "2") (pinfunction "2_2") (pintype "passive"))
      (node (ref "R20") (pin "2") (pinfunction "2_2") (pintype "passive"))
    )
    (net (code "42") (name "Net-(D4C-VREF)") (class "Default")
      (node (ref "C72") (pin "1") (pinfunction "1_1") (pintype "power_in"))
      (node (ref "D4") (pin "37") (pinfunction "VREF_37") (pintype "passive"))
    )
    (net (code "43") (name "Net-(VD4-C)") (class "Default")
      (node (ref "R21") (pin "2") (pinfunction "2_2") (pintype "passive"))
      (node (ref "VD4") (pin "2") (pinfunction "C_2") (pintype "passive"))
    )
    (net (code "44") (name "unconnected-(D4C-DVSOK-Pad54)") (class "Default")
      (node (ref "D4") (pin "54") (pinfunction "DVSOK_54") (pintype "passive"))
    )
    (net (code "45") (name "unconnected-(D4C-NC-Pad47)") (class "Default")
      (node (ref "D4") (pin "47") (pinfunction "NC_47") (pintype "passive"))
    )
    (net (code "46") (name "unconnected-(D4C-NC-Pad48)") (class "Default")
      (node (ref "D4") (pin "48") (pinfunction "NC_48") (pintype "passive"))
    )
  )
)
